# RS-485_SN65HVD72DRBR.net
KiCad netlist of a schematic drawn in Altium Designer
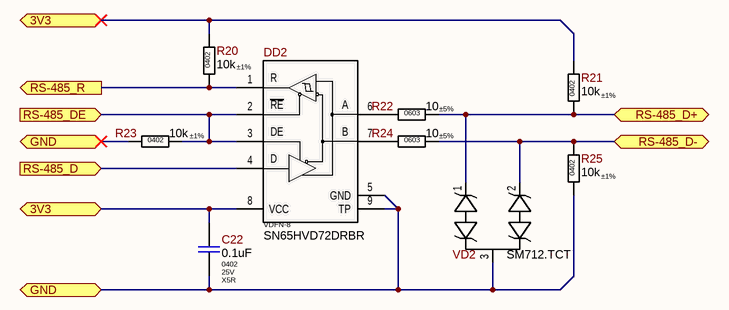
[diagram p0: RS-485_SN65HVD72DRBR.SchDoc]

(export (version "E")
  (design (tool "Eeschema 10.0.6"))
  (components
    (comp (ref "C22")
      (value "0.1uF")
      (footprint "C_CERAMIC_0402_HI")
      (description "100nF 25V X5R ±10% 0402 Ceramic Capacitor RoHS")
      (fields
        (field (name "PACKAGE") "0402")
        (field (name "VOLTAGE") "25V")
        (field (name "DIELECTRIC TYPE") "X5R")
        (field (name "PART NUMBER") "CL05A104KA5NNNC")
        (field (name "MANUFACTURER") "Samsung Electro-Mechanics")
      )
      (libsource (lib "EL.XXX.T01") (part "CL05A104KA5NNNC"))
    )
    (comp (ref "DD2")
      (value "SN65HVD72DRBR")
      (footprint "TI-SON8-65P300X100_HS")
      (description "3.3V 1/1 Transceiver Half RS422 Up to 250 kbps, RS485 With IEC ESD protection, SON-8")
      (fields
        (field (name "PACKAGE") "VDFN-8")
        (field (name "PART NUMBER") "SN65HVD72DRBR")
        (field (name "MANUFACTURER") "Texas Instruments")
      )
      (libsource (lib "EL.XXX.T01") (part "SN65HVD72DRBR"))
    )
    (comp (ref "R20")
      (value "10k")
      (footprint "R_ANY_CHIP_0402_MED")
      (description "10 kOhms ±1% 1/16W 0402 Thick Film Resistor")
      (fields
        (field (name "TOLERANCE") "±1%")
        (field (name "PACKAGE") "0402")
        (field (name "PART NUMBER") "RC0402FR-0710KL")
        (field (name "MANUFACTURER") "Yageo")
      )
      (libsource (lib "EL.XXX.T01") (part "RC0402FR-0710KL"))
    )
    (comp (ref "R21")
      (value "10k")
      (footprint "R_ANY_CHIP_0402_MED")
      (description "10 kOhms ±1% 1/16W 0402 Thick Film Resistor")
      (fields
        (field (name "TOLERANCE") "±1%")
        (field (name "PACKAGE") "0402")
        (field (name "PART NUMBER") "RC0402FR-0710KL")
        (field (name "MANUFACTURER") "Yageo")
      )
      (libsource (lib "EL.XXX.T01") (part "RC0402FR-0710KL"))
    )
    (comp (ref "R22")
      (value "10")
      (footprint "R_ANY_CHIP_0603_MED")
      (description "10 Ohms ±5%, 1/10W 0603 Thick Film Resistor")
      (fields
        (field (name "TOLERANCE") "±5%")
        (field (name "PACKAGE") "0603")
        (field (name "PART NUMBER") "RC0603JR-0710RL")
        (field (name "MANUFACTURER") "Yageo")
      )
      (libsource (lib "EL.XXX.T01") (part "RC0603JR-0710RL"))
    )
    (comp (ref "R23")
      (value "10k")
      (footprint "R_ANY_CHIP_0402_MED")
      (description "10 kOhms ±1% 1/16W 0402 Thick Film Resistor")
      (fields
        (field (name "TOLERANCE") "±1%")
        (field (name "PACKAGE") "0402")
        (field (name "PART NUMBER") "RC0402FR-0710KL")
        (field (name "MANUFACTURER") "Yageo")
      )
      (libsource (lib "EL.XXX.T01") (part "RC0402FR-0710KL"))
    )
    (comp (ref "R24")
      (value "10")
      (footprint "R_ANY_CHIP_0603_MED")
      (description "10 Ohms ±5%, 1/10W 0603 Thick Film Resistor")
      (fields
        (field (name "TOLERANCE") "±5%")
        (field (name "PACKAGE") "0603")
        (field (name "PART NUMBER") "RC0603JR-0710RL")
        (field (name "MANUFACTURER") "Yageo")
      )
      (libsource (lib "EL.XXX.T01") (part "RC0603JR-0710RL"))
    )
    (comp (ref "R25")
      (value "10k")
      (footprint "R_ANY_CHIP_0402_MED")
      (description "10 kOhms ±1% 1/16W 0402 Thick Film Resistor")
      (fields
        (field (name "TOLERANCE") "±1%")
        (field (name "PACKAGE") "0402")
        (field (name "PART NUMBER") "RC0402FR-0710KL")
        (field (name "MANUFACTURER") "Yageo")
      )
      (libsource (lib "EL.XXX.T01") (part "RC0402FR-0710KL"))
    )
    (comp (ref "VD2")
      (value "SM712.TCT")
      (footprint "SOT-23_MED")
      (description "TVS Diode 26V and 19V Clamp, 21A and 38A (8/20us) Ipp, SOT-23")
      (fields
        (field (name "PART NUMBER") "SM712.TCT")
        (field (name "MANUFACTURER") "Semtech")
        (field (name "VOLTAGE") "13.3V, 7.5V")
      )
      (libsource (lib "EL.XXX.T01") (part "SM712.TCT"))
    )
  )
  (nets
    (net (code "1") (name "/3V3") (class "Default")
      (node (ref "C22") (pin "1") (pinfunction "1_1") (pintype "passive"))
      (node (ref "DD2") (pin "8") (pinfunction "VCC_8") (pintype "passive"))
      (node (ref "R20") (pin "1") (pintype "passive"))
      (node (ref "R21") (pin "1") (pintype "passive"))
    )
    (net (code "2") (name "/GND") (class "Default")
      (node (ref "C22") (pin "2") (pinfunction "2_2") (pintype "passive"))
      (node (ref "DD2") (pin "5") (pinfunction "GND_5") (pintype "passive"))
      (node (ref "DD2") (pin "9") (pinfunction "TP_9") (pintype "passive"))
      (node (ref "R23") (pin "2") (pintype "passive"))
      (node (ref "R25") (pin "2") (pintype "passive"))
      (node (ref "VD2") (pin "3") (pintype "passive"))
    )
    (net (code "3") (name "/RS-485_D") (class "Default")
      (node (ref "DD2") (pin "4") (pinfunction "DI_4") (pintype "passive"))
    )
    (net (code "4") (name "/RS-485_D+") (class "Default")
      (node (ref "R21") (pin "2") (pintype "passive"))
      (node (ref "R22") (pin "2") (pintype "passive"))
      (node (ref "VD2") (pin "1") (pintype "passive"))
    )
    (net (code "5") (name "/RS-485_D-") (class "Default")
      (node (ref "R24") (pin "2") (pintype "passive"))
      (node (ref "R25") (pin "1") (pintype "passive"))
      (node (ref "VD2") (pin "2") (pintype "passive"))
    )
    (net (code "6") (name "/RS-485_DE") (class "Default")
      (node (ref "DD2") (pin "2") (pinfunction "~{RE}_2") (pintype "passive"))
      (node (ref "DD2") (pin "3") (pinfunction "DE_3") (pintype "passive"))
      (node (ref "R23") (pin "1") (pintype "passive"))
    )
    (net (code "7") (name "/RS-485_R") (class "Default")
      (node (ref "DD2") (pin "1") (pinfunction "RO_1") (pintype "passive"))
      (node (ref "R20") (pin "2") (pintype "passive"))
    )
    (net (code "8") (name "Net-(DD2-A)") (class "Default")
      (node (ref "DD2") (pin "6") (pinfunction "A_6") (pintype "passive"))
      (node (ref "R22") (pin "1") (pintype "passive"))
    )
    (net (code "9") (name "Net-(DD2-B)") (class "Default")
      (node (ref "DD2") (pin "7") (pinfunction "B_7") (pintype "passive"))
      (node (ref "R24") (pin "1") (pintype "passive"))
    )
  )
)
